# Retificador.net
KiCad netlist of a schematic drawn in Altium Designer
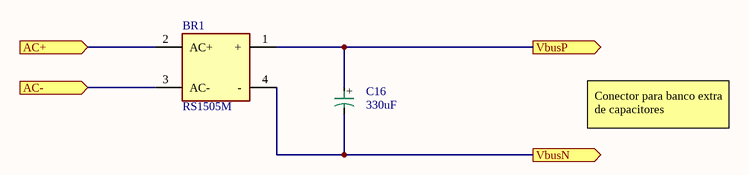
[diagram p0: Retificador.SchDoc]

(export (version "E")
  (design (tool "Eeschema 10.0.6"))
  (components
    (comp (ref "BR1")
      (value "RS1505M")
      (footprint "RS1505M_BOT")
      (description "Bridge Rectifier")
      (fields (field (name "MOUSER PART NUMBER") "583-RS1505M"))
      (libsource (lib "SamacSys") (part "RS1505M"))
    )
    (comp (ref "C16")
      (value "330uF")
      (footprint "CAP ALU D30 A50")
      (description "Capacitor 30x50 mm")
      (fields (field (name "Comment") "Cap 30x50 mm"))
      (libsource (lib "RLC_Integrated_Library") (part "Capacitor ALU 30x50 mm"))
    )
  )
  (nets
    (net (code "1") (name "/AC+") (class "Default")
      (node (ref "BR1") (pin "2") (pinfunction "AC+_2") (pintype "passive"))
    )
    (net (code "2") (name "/AC-") (class "Default")
      (node (ref "BR1") (pin "3") (pinfunction "AC-_3") (pintype "passive"))
    )
    (net (code "3") (name "/VbusN") (class "Default")
      (node (ref "BR1") (pin "4") (pinfunction "-_4") (pintype "passive"))
      (node (ref "C16") (pin "2") (pinfunction "2_2") (pintype "passive"))
    )
    (net (code "4") (name "/VbusP") (class "Default")
      (node (ref "BR1") (pin "1") (pinfunction "+_1") (pintype "passive"))
      (node (ref "C16") (pin "1") (pinfunction "1_1") (pintype "passive"))
    )
  )
)
